# Strvo_Tester_STM_v3.net
KiCad netlist of a schematic drawn in EAGLE
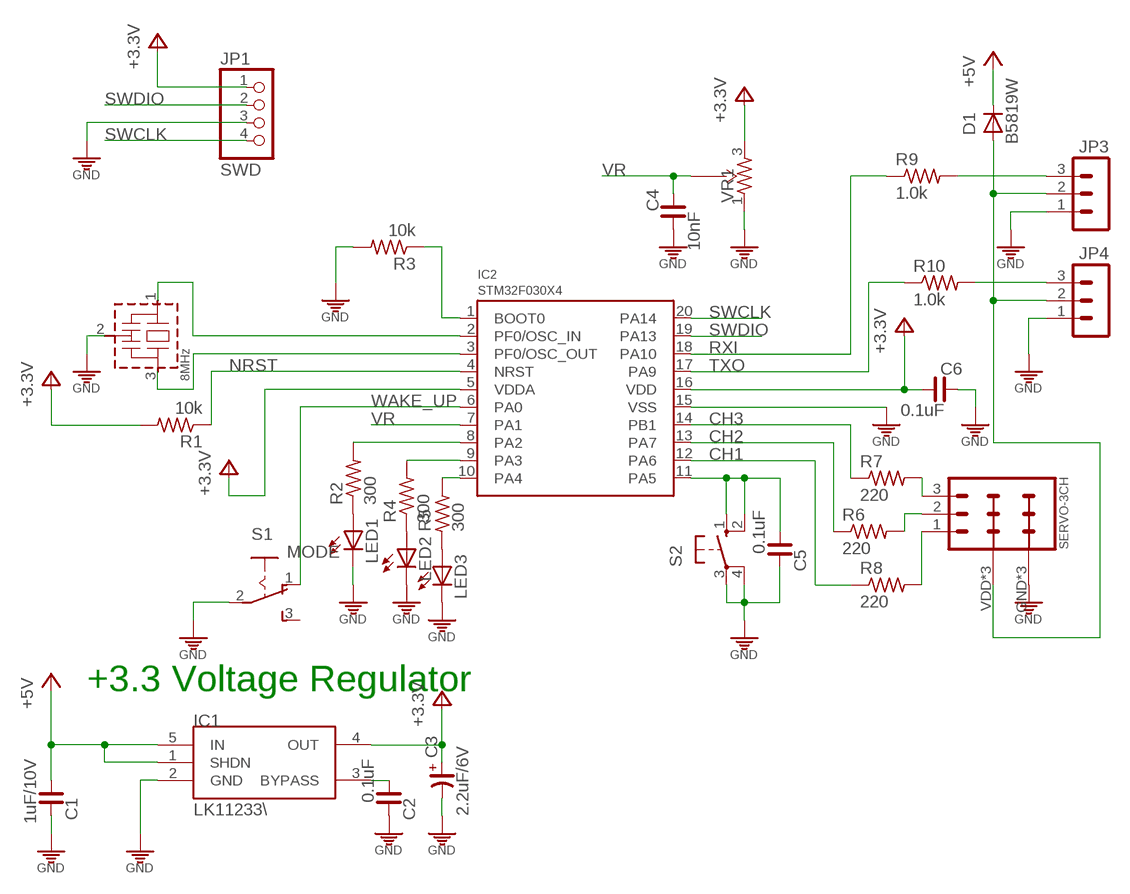
[diagram p0: schematic, sheet 1]

(export (version "E")
  (design (tool "Eeschema 10.0.6"))
  (components
    (comp (ref "C1")
      (value "1uF/10V")
      (footprint "eagle-import:C0603")
      (libsource (lib "eagle-import") (part "C_0603"))
    )
    (comp (ref "C2")
      (value "0.1uF")
      (footprint "eagle-import:C0603")
      (libsource (lib "eagle-import") (part "C_0603"))
    )
    (comp (ref "C3")
      (value "2.2uF/6V")
      (footprint "eagle-import:C2012_T")
      (libsource (lib "eagle-import") (part "CP_2012"))
    )
    (comp (ref "C4")
      (value "10nF")
      (footprint "eagle-import:C0603")
      (libsource (lib "eagle-import") (part "C_0603"))
    )
    (comp (ref "C5")
      (value "0.1uF")
      (footprint "eagle-import:C0603")
      (libsource (lib "eagle-import") (part "C_0603"))
    )
    (comp (ref "C6")
      (value "0.1uF")
      (footprint "eagle-import:C0603")
      (libsource (lib "eagle-import") (part "C_0603"))
    )
    (comp (ref "D1")
      (value "B5819W")
      (footprint "eagle-import:SOD323")
      (libsource (lib "eagle-import") (part "B5189WN"))
    )
    (comp (ref "IC1")
      (value "LK11233\\")
      (footprint "eagle-import:SOT23-5L")
      (libsource (lib "eagle-import") (part "LK112XX"))
    )
    (comp (ref "IC2")
      (value "STM32F030X4")
      (footprint "eagle-import:TSSOP20")
      (libsource (lib "eagle-import") (part "STM32F030X4"))
    )
    (comp (ref "JP1")
      (value "SWD")
      (footprint "eagle-import:1X04M")
      (libsource (lib "eagle-import") (part "PINHD-1X4M"))
    )
    (comp (ref "JP2")
      (value "SERVO-3CH")
      (footprint "eagle-import:SERVO-3CH1")
      (libsource (lib "eagle-import") (part "SERVO-3CH"))
    )
    (comp (ref "JP3")
      (value "MA03-1SMALL")
      (footprint "eagle-import:MA03-1-S")
      (libsource (lib "eagle-import") (part "MA03-1SMALL"))
    )
    (comp (ref "JP4")
      (value "MA03-1SMALL")
      (footprint "eagle-import:MA03-1-S")
      (libsource (lib "eagle-import") (part "MA03-1SMALL"))
    )
    (comp (ref "LED1")
      (value "LED3MM")
      (footprint "eagle-import:LED3MM")
      (libsource (lib "eagle-import") (part "LED3MM"))
    )
    (comp (ref "LED2")
      (value "LED3MM")
      (footprint "eagle-import:LED3MM")
      (libsource (lib "eagle-import") (part "LED3MM"))
    )
    (comp (ref "LED3")
      (value "LED3MM")
      (footprint "eagle-import:LED3MM")
      (libsource (lib "eagle-import") (part "LED3MM"))
    )
    (comp (ref "Q1")
      (value "8MHz")
      (footprint "eagle-import:CSTLA_X")
      (libsource (lib "eagle-import") (part "X-TAL-SMALLCSTCE16M00V53"))
    )
    (comp (ref "R1")
      (value "10k")
      (footprint "eagle-import:R0603")
      (libsource (lib "eagle-import") (part "R-US_R1608"))
    )
    (comp (ref "R2")
      (value "300")
      (footprint "eagle-import:R0603")
      (libsource (lib "eagle-import") (part "R-US_R1608"))
    )
    (comp (ref "R3")
      (value "10k")
      (footprint "eagle-import:R0603")
      (libsource (lib "eagle-import") (part "R-US_R1608"))
    )
    (comp (ref "R4")
      (value "300")
      (footprint "eagle-import:R0603")
      (libsource (lib "eagle-import") (part "R-US_R1608"))
    )
    (comp (ref "R5")
      (value "300")
      (footprint "eagle-import:R0603")
      (libsource (lib "eagle-import") (part "R_0603"))
    )
    (comp (ref "R6")
      (value "220")
      (footprint "eagle-import:R0603")
      (libsource (lib "eagle-import") (part "R-US_R1608"))
    )
    (comp (ref "R7")
      (value "220")
      (footprint "eagle-import:R0603")
      (libsource (lib "eagle-import") (part "R-US_R1608"))
    )
    (comp (ref "R8")
      (value "220")
      (footprint "eagle-import:R0603")
      (libsource (lib "eagle-import") (part "R-US_R1608"))
    )
    (comp (ref "R9")
      (value "1.0k")
      (footprint "eagle-import:R0603")
      (libsource (lib "eagle-import") (part "R-US_R1608"))
    )
    (comp (ref "R10")
      (value "1.0k")
      (footprint "eagle-import:R0603")
      (libsource (lib "eagle-import") (part "R-US_R1608"))
    )
    (comp (ref "S1")
      (value "MODE")
      (footprint "eagle-import:255SB")
      (libsource (lib "eagle-import") (part "IMMS"))
    )
    (comp (ref "S2")
      (value "10-XX")
      (footprint "eagle-import:B3F-10XX")
      (fields (field (name "MPN") "B3F-1000"))
      (libsource (lib "eagle-import") (part "10-XX"))
    )
    (comp (ref "VR1")
      (value "R-TRIMMER-SMDPTV")
      (footprint "eagle-import:PTV09")
      (libsource (lib "eagle-import") (part "R-TRIMMER-SMDPTV"))
    )
  )
  (nets
    (net (code "1") (name "+3V3") (class "Default")
      (node (ref "C3") (pin "+") (pinfunction "+_+") (pintype "passive"))
      (node (ref "C6") (pin "2") (pinfunction "2_2") (pintype "passive"))
      (node (ref "IC1") (pin "4") (pinfunction "OUT_4") (pintype "power_in"))
      (node (ref "IC2") (pin "16") (pinfunction "VDD_16") (pintype "power_in"))
      (node (ref "IC2") (pin "5") (pinfunction "VDDA_5") (pintype "power_in"))
      (node (ref "JP1") (pin "1") (pinfunction "1_1") (pintype "passive"))
      (node (ref "R1") (pin "2") (pinfunction "2_2") (pintype "passive"))
      (node (ref "VR1") (pin "3") (pinfunction "3_3") (pintype "passive"))
    )
    (net (code "2") (name "+5V") (class "Default")
      (node (ref "C1") (pin "2") (pinfunction "2_2") (pintype "passive"))
      (node (ref "D1") (pin "C") (pinfunction "C_C") (pintype "passive"))
      (node (ref "IC1") (pin "1") (pinfunction "SHDN_1") (pintype "passive"))
      (node (ref "IC1") (pin "5") (pinfunction "IN_5") (pintype "power_in"))
    )
    (net (code "3") (name "/CH1") (class "Default")
      (node (ref "IC2") (pin "12") (pinfunction "PA6_12") (pintype "bidirectional"))
      (node (ref "R8") (pin "1") (pinfunction "1_1") (pintype "passive"))
    )
    (net (code "4") (name "/CH2") (class "Default")
      (node (ref "IC2") (pin "13") (pinfunction "PA7_13") (pintype "bidirectional"))
      (node (ref "R6") (pin "1") (pinfunction "1_1") (pintype "passive"))
    )
    (net (code "5") (name "/CH3") (class "Default")
      (node (ref "IC2") (pin "14") (pinfunction "PB1_14") (pintype "bidirectional"))
      (node (ref "R7") (pin "1") (pinfunction "1_1") (pintype "passive"))
    )
    (net (code "6") (name "/NRST") (class "Default")
      (node (ref "IC2") (pin "4") (pinfunction "NRST_4") (pintype "bidirectional"))
      (node (ref "R1") (pin "1") (pinfunction "1_1") (pintype "passive"))
    )
    (net (code "7") (name "/RXI") (class "Default")
      (node (ref "IC2") (pin "18") (pinfunction "PA10_18") (pintype "bidirectional"))
      (node (ref "R9") (pin "1") (pinfunction "1_1") (pintype "passive"))
    )
    (net (code "8") (name "/SWCLK") (class "Default")
      (node (ref "IC2") (pin "20") (pinfunction "PA14_20") (pintype "bidirectional"))
      (node (ref "JP1") (pin "4") (pinfunction "4_4") (pintype "passive"))
    )
    (net (code "9") (name "/SWDIO") (class "Default")
      (node (ref "IC2") (pin "19") (pinfunction "PA13_19") (pintype "bidirectional"))
      (node (ref "JP1") (pin "2") (pinfunction "2_2") (pintype "passive"))
    )
    (net (code "10") (name "/TXO") (class "Default")
      (node (ref "IC2") (pin "17") (pinfunction "PA9_17") (pintype "bidirectional"))
      (node (ref "R10") (pin "1") (pinfunction "1_1") (pintype "passive"))
    )
    (net (code "11") (name "/VR") (class "Default")
      (node (ref "C4") (pin "1") (pinfunction "1_1") (pintype "passive"))
      (node (ref "IC2") (pin "7") (pinfunction "PA1_7") (pintype "bidirectional"))
      (node (ref "VR1") (pin "2") (pinfunction "2_2") (pintype "passive"))
    )
    (net (code "12") (name "/WAKE_UP") (class "Default")
      (node (ref "IC2") (pin "6") (pinfunction "PA0_6") (pintype "bidirectional"))
      (node (ref "S1") (pin "1") (pinfunction "O_1") (pintype "passive"))
    )
    (net (code "13") (name "GND") (class "Default")
      (node (ref "C1") (pin "1") (pinfunction "1_1") (pintype "passive"))
      (node (ref "C2") (pin "1") (pinfunction "1_1") (pintype "passive"))
      (node (ref "C3") (pin "-") (pinfunction "-_-") (pintype "passive"))
      (node (ref "C4") (pin "2") (pinfunction "2_2") (pintype "passive"))
      (node (ref "C5") (pin "1") (pinfunction "1_1") (pintype "passive"))
      (node (ref "C6") (pin "1") (pinfunction "1_1") (pintype "passive"))
      (node (ref "IC1") (pin "2") (pinfunction "GND_2") (pintype "power_in"))
      (node (ref "IC2") (pin "15") (pinfunction "VSS_15") (pintype "power_in"))
      (node (ref "JP1") (pin "3") (pinfunction "3_3") (pintype "passive"))
      (node (ref "JP2") (pin "GND") (pinfunction "GND_GND") (pintype "passive"))
      (node (ref "JP2") (pin "GND@1") (pinfunction "GND_GND@1") (pintype "passive"))
      (node (ref "JP2") (pin "GND@2") (pinfunction "GND_GND@2") (pintype "passive"))
      (node (ref "JP3") (pin "1") (pinfunction "1_1") (pintype "passive"))
      (node (ref "JP4") (pin "1") (pinfunction "1_1") (pintype "passive"))
      (node (ref "LED1") (pin "K") (pinfunction "C_K") (pintype "passive"))
      (node (ref "LED2") (pin "K") (pinfunction "C_K") (pintype "passive"))
      (node (ref "LED3") (pin "K") (pinfunction "C_K") (pintype "passive"))
      (node (ref "Q1") (pin "2") (pinfunction "GND_2") (pintype "power_in"))
      (node (ref "R3") (pin "2") (pinfunction "2_2") (pintype "passive"))
      (node (ref "S1") (pin "2") (pinfunction "P_2") (pintype "passive"))
      (node (ref "S2") (pin "3") (pinfunction "P_3") (pintype "passive"))
      (node (ref "S2") (pin "4") (pinfunction "P1_4") (pintype "passive"))
      (node (ref "VR1") (pin "1") (pinfunction "1_1") (pintype "passive"))
    )
    (net (code "14") (name "Net-(D1-PadA)") (class "Default")
      (node (ref "D1") (pin "A") (pinfunction "A_A") (pintype "passive"))
      (node (ref "JP2") (pin "VDD") (pinfunction "+5V_VDD") (pintype "passive"))
      (node (ref "JP2") (pin "VDD@1") (pinfunction "+5V_VDD@1") (pintype "passive"))
      (node (ref "JP2") (pin "VDD@2") (pinfunction "+5V_VDD@2") (pintype "passive"))
      (node (ref "JP3") (pin "2") (pinfunction "2_2") (pintype "passive"))
      (node (ref "JP4") (pin "2") (pinfunction "2_2") (pintype "passive"))
    )
    (net (code "15") (name "Net-(IC1-BYPASS)") (class "Default")
      (node (ref "C2") (pin "2") (pinfunction "2_2") (pintype "passive"))
      (node (ref "IC1") (pin "3") (pinfunction "BYPASS_3") (pintype "passive"))
    )
    (net (code "16") (name "Net-(IC2-BOOT0)") (class "Default")
      (node (ref "IC2") (pin "1") (pinfunction "BOOT0_1") (pintype "bidirectional"))
      (node (ref "R3") (pin "1") (pinfunction "1_1") (pintype "passive"))
    )
    (net (code "17") (name "Net-(IC2-PA2)") (class "Default")
      (node (ref "IC2") (pin "8") (pinfunction "PA2_8") (pintype "bidirectional"))
      (node (ref "R2") (pin "2") (pinfunction "2_2") (pintype "passive"))
    )
    (net (code "18") (name "Net-(IC2-PA3)") (class "Default")
      (node (ref "IC2") (pin "9") (pinfunction "PA3_9") (pintype "bidirectional"))
      (node (ref "R4") (pin "2") (pinfunction "2_2") (pintype "passive"))
    )
    (net (code "19") (name "Net-(IC2-PA4)") (class "Default")
      (node (ref "IC2") (pin "10") (pinfunction "PA4_10") (pintype "bidirectional"))
      (node (ref "R5") (pin "2") (pinfunction "2_2") (pintype "passive"))
    )
    (net (code "20") (name "Net-(IC2-PA5)") (class "Default")
      (node (ref "C5") (pin "2") (pinfunction "2_2") (pintype "passive"))
      (node (ref "IC2") (pin "11") (pinfunction "PA5_11") (pintype "bidirectional"))
      (node (ref "S2") (pin "1") (pinfunction "S_1") (pintype "passive"))
      (node (ref "S2") (pin "2") (pinfunction "S1_2") (pintype "passive"))
    )
    (net (code "21") (name "Net-(IC2-PF0{slash}OSC_IN)") (class "Default")
      (node (ref "IC2") (pin "2") (pinfunction "PF0/OSC_IN_2") (pintype "bidirectional"))
      (node (ref "Q1") (pin "1") (pinfunction "IN_1") (pintype "output"))
    )
    (net (code "22") (name "Net-(IC2-PF0{slash}OSC_OUT)") (class "Default")
      (node (ref "IC2") (pin "3") (pinfunction "PF0/OSC_OUT_3") (pintype "bidirectional"))
      (node (ref "Q1") (pin "3") (pinfunction "OUT_3") (pintype "input"))
    )
    (net (code "23") (name "Net-(JP2-Pad1)") (class "Default")
      (node (ref "JP2") (pin "1") (pinfunction "1_1") (pintype "passive"))
      (node (ref "R8") (pin "2") (pinfunction "2_2") (pintype "passive"))
    )
    (net (code "24") (name "Net-(JP2-Pad2)") (class "Default")
      (node (ref "JP2") (pin "2") (pinfunction "2_2") (pintype "passive"))
      (node (ref "R6") (pin "2") (pinfunction "2_2") (pintype "passive"))
    )
    (net (code "25") (name "Net-(JP2-Pad3)") (class "Default")
      (node (ref "JP2") (pin "3") (pinfunction "3_3") (pintype "passive"))
      (node (ref "R7") (pin "2") (pinfunction "2_2") (pintype "passive"))
    )
    (net (code "26") (name "Net-(JP3-Pad3)") (class "Default")
      (node (ref "JP3") (pin "3") (pinfunction "3_3") (pintype "passive"))
      (node (ref "R9") (pin "2") (pinfunction "2_2") (pintype "passive"))
    )
    (net (code "27") (name "Net-(JP4-Pad3)") (class "Default")
      (node (ref "JP4") (pin "3") (pinfunction "3_3") (pintype "passive"))
      (node (ref "R10") (pin "2") (pinfunction "2_2") (pintype "passive"))
    )
    (net (code "28") (name "Net-(LED1-PadA)") (class "Default")
      (node (ref "LED1") (pin "A") (pinfunction "A_A") (pintype "passive"))
      (node (ref "R2") (pin "1") (pinfunction "1_1") (pintype "passive"))
    )
    (net (code "29") (name "Net-(LED2-PadA)") (class "Default")
      (node (ref "LED2") (pin "A") (pinfunction "A_A") (pintype "passive"))
      (node (ref "R4") (pin "1") (pinfunction "1_1") (pintype "passive"))
    )
    (net (code "30") (name "Net-(LED3-PadA)") (class "Default")
      (node (ref "LED3") (pin "A") (pinfunction "A_A") (pintype "passive"))
      (node (ref "R5") (pin "1") (pinfunction "1_1") (pintype "passive"))
    )
    (net (code "31") (name "unconnected-(S1-S-Pad3)") (class "Default")
      (node (ref "S1") (pin "3") (pinfunction "S_3") (pintype "passive"))
    )
  )
)
